# CntrlBoard.net
KiCad netlist of a schematic drawn in EAGLE
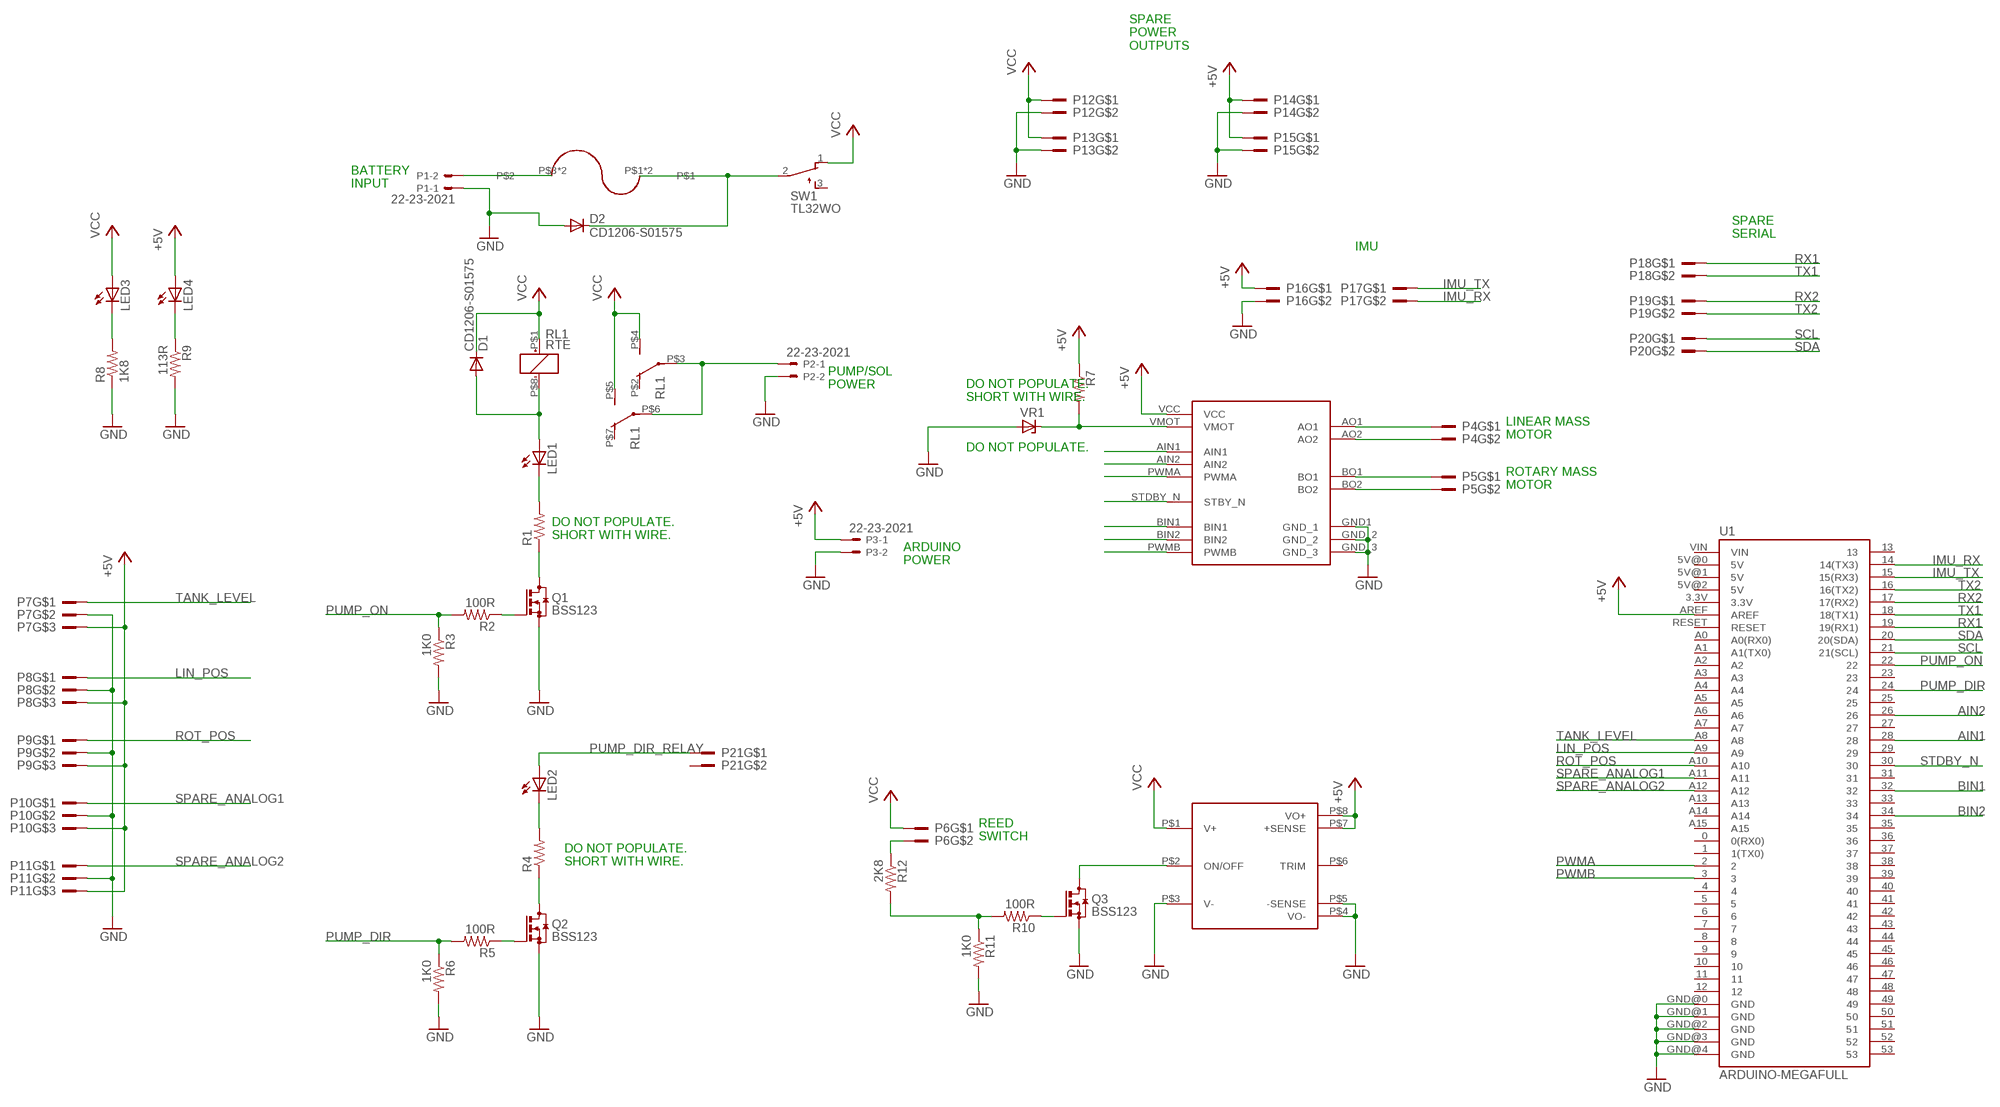
[diagram p0: schematic, sheet 1]

(export (version "E")
  (design (tool "Eeschema 10.0.6"))
  (components
    (comp (ref "D1")
      (value "CD1206-S01575")
      (footprint "eagle-import:CD1206")
      (libsource (lib "eagle-import") (part "CD1206-S01575"))
    )
    (comp (ref "D2")
      (value "CD1206-S01575")
      (footprint "eagle-import:CD1206")
      (libsource (lib "eagle-import") (part "CD1206-S01575"))
    )
    (comp (ref "LED1")
      (value "LEDCHIPLED_1206")
      (footprint "eagle-import:CHIPLED_1206")
      (libsource (lib "eagle-import") (part "LEDCHIPLED_1206"))
    )
    (comp (ref "LED2")
      (value "LEDCHIPLED_1206")
      (footprint "eagle-import:CHIPLED_1206")
      (libsource (lib "eagle-import") (part "LEDCHIPLED_1206"))
    )
    (comp (ref "LED3")
      (value "LEDCHIPLED_1206")
      (footprint "eagle-import:CHIPLED_1206")
      (libsource (lib "eagle-import") (part "LEDCHIPLED_1206"))
    )
    (comp (ref "LED4")
      (value "LEDCHIPLED_1206")
      (footprint "eagle-import:CHIPLED_1206")
      (libsource (lib "eagle-import") (part "LEDCHIPLED_1206"))
    )
    (comp (ref "P1")
      (value "22-23-2021")
      (footprint "eagle-import:22-23-2021")
      (fields (field (name "MF") "MOLEX"))
      (libsource (lib "eagle-import") (part "22-23-2021"))
    )
    (comp (ref "P2")
      (value "22-23-2021")
      (footprint "eagle-import:22-23-2021")
      (fields (field (name "MF") "MOLEX"))
      (libsource (lib "eagle-import") (part "22-23-2021"))
    )
    (comp (ref "P3")
      (value "22-23-2021")
      (footprint "eagle-import:22-23-2021")
      (fields (field (name "MF") "MOLEX"))
      (libsource (lib "eagle-import") (part "22-23-2021"))
    )
    (comp (ref "P4")
      (value "DF3A-2P-2DSA")
      (footprint "eagle-import:DF3A-2P-2DSA")
      (libsource (lib "eagle-import") (part "DF3A-2P-2DSA"))
    )
    (comp (ref "P5")
      (value "DF3A-2P-2DSA")
      (footprint "eagle-import:DF3A-2P-2DSA")
      (libsource (lib "eagle-import") (part "DF3A-2P-2DSA"))
    )
    (comp (ref "P6")
      (value "DF3A-2P-2DSA")
      (footprint "eagle-import:DF3A-2P-2DSA")
      (libsource (lib "eagle-import") (part "DF3A-2P-2DSA"))
    )
    (comp (ref "P7")
      (value "3PIN2MMPITCH")
      (footprint "eagle-import:3PIN_2MMPITCH")
      (libsource (lib "eagle-import") (part "3PIN2MMPITCH"))
    )
    (comp (ref "P8")
      (value "3PIN2MMPITCH")
      (footprint "eagle-import:3PIN_2MMPITCH")
      (libsource (lib "eagle-import") (part "3PIN2MMPITCH"))
    )
    (comp (ref "P9")
      (value "3PIN2MMPITCH")
      (footprint "eagle-import:3PIN_2MMPITCH")
      (libsource (lib "eagle-import") (part "3PIN2MMPITCH"))
    )
    (comp (ref "P10")
      (value "3PIN2MMPITCH")
      (footprint "eagle-import:3PIN_2MMPITCH")
      (libsource (lib "eagle-import") (part "3PIN2MMPITCH"))
    )
    (comp (ref "P11")
      (value "3PIN2MMPITCH")
      (footprint "eagle-import:3PIN_2MMPITCH")
      (libsource (lib "eagle-import") (part "3PIN2MMPITCH"))
    )
    (comp (ref "P12")
      (value "DF3A-2P-2DSA")
      (footprint "eagle-import:DF3A-2P-2DSA")
      (libsource (lib "eagle-import") (part "DF3A-2P-2DSA"))
    )
    (comp (ref "P13")
      (value "DF3A-2P-2DSA")
      (footprint "eagle-import:DF3A-2P-2DSA")
      (libsource (lib "eagle-import") (part "DF3A-2P-2DSA"))
    )
    (comp (ref "P14")
      (value "DF3A-2P-2DSA")
      (footprint "eagle-import:DF3A-2P-2DSA")
      (libsource (lib "eagle-import") (part "DF3A-2P-2DSA"))
    )
    (comp (ref "P15")
      (value "DF3A-2P-2DSA")
      (footprint "eagle-import:DF3A-2P-2DSA")
      (libsource (lib "eagle-import") (part "DF3A-2P-2DSA"))
    )
    (comp (ref "P16")
      (value "DF3A-2P-2DSA")
      (footprint "eagle-import:DF3A-2P-2DSA")
      (libsource (lib "eagle-import") (part "DF3A-2P-2DSA"))
    )
    (comp (ref "P17")
      (value "DF3A-2P-2DSA")
      (footprint "eagle-import:DF3A-2P-2DSA")
      (libsource (lib "eagle-import") (part "DF3A-2P-2DSA"))
    )
    (comp (ref "P18")
      (value "DF3A-2P-2DSA")
      (footprint "eagle-import:DF3A-2P-2DSA")
      (libsource (lib "eagle-import") (part "DF3A-2P-2DSA"))
    )
    (comp (ref "P19")
      (value "DF3A-2P-2DSA")
      (footprint "eagle-import:DF3A-2P-2DSA")
      (libsource (lib "eagle-import") (part "DF3A-2P-2DSA"))
    )
    (comp (ref "P20")
      (value "DF3A-2P-2DSA")
      (footprint "eagle-import:DF3A-2P-2DSA")
      (libsource (lib "eagle-import") (part "DF3A-2P-2DSA"))
    )
    (comp (ref "P21")
      (value "DF3A-2P-2DSA")
      (footprint "eagle-import:DF3A-2P-2DSA")
      (libsource (lib "eagle-import") (part "DF3A-2P-2DSA"))
    )
    (comp (ref "PS1")
      (value "KHHD006A0A41Z")
      (footprint "eagle-import:KHHD006A0A41Z")
      (libsource (lib "eagle-import") (part "KHHD006A0A41Z"))
    )
    (comp (ref "Q1")
      (value "BSS123")
      (footprint "eagle-import:SOT23")
      (libsource (lib "eagle-import") (part "BSS123"))
    )
    (comp (ref "Q2")
      (value "BSS123")
      (footprint "eagle-import:SOT23")
      (libsource (lib "eagle-import") (part "BSS123"))
    )
    (comp (ref "Q3")
      (value "BSS123")
      (footprint "eagle-import:SOT23")
      (libsource (lib "eagle-import") (part "BSS123"))
    )
    (comp (ref "R1")
      (value "R-US_R1206")
      (footprint "eagle-import:R1206")
      (libsource (lib "eagle-import") (part "R-US_R1206"))
    )
    (comp (ref "R2")
      (value "100R")
      (footprint "eagle-import:R1206")
      (libsource (lib "eagle-import") (part "R-US_R1206"))
    )
    (comp (ref "R3")
      (value "1K0")
      (footprint "eagle-import:R1206")
      (libsource (lib "eagle-import") (part "R-US_R1206"))
    )
    (comp (ref "R4")
      (value "R-US_R1206")
      (footprint "eagle-import:R1206")
      (libsource (lib "eagle-import") (part "R-US_R1206"))
    )
    (comp (ref "R5")
      (value "100R")
      (footprint "eagle-import:R1206")
      (libsource (lib "eagle-import") (part "R-US_R1206"))
    )
    (comp (ref "R6")
      (value "1K0")
      (footprint "eagle-import:R1206")
      (libsource (lib "eagle-import") (part "R-US_R1206"))
    )
    (comp (ref "R7")
      (value "R-US_R1206")
      (footprint "eagle-import:R1206")
      (libsource (lib "eagle-import") (part "R-US_R1206"))
    )
    (comp (ref "R8")
      (value "1K8")
      (footprint "eagle-import:R1210")
      (libsource (lib "eagle-import") (part "R-US_R1210"))
    )
    (comp (ref "R9")
      (value "113R")
      (footprint "eagle-import:R1206")
      (libsource (lib "eagle-import") (part "R-US_R1206"))
    )
    (comp (ref "R10")
      (value "100R")
      (footprint "eagle-import:R1206")
      (libsource (lib "eagle-import") (part "R-US_R1206"))
    )
    (comp (ref "R11")
      (value "1K0")
      (footprint "eagle-import:R1206")
      (libsource (lib "eagle-import") (part "R-US_R1206"))
    )
    (comp (ref "R12")
      (value "2K8")
      (footprint "eagle-import:R1206")
      (libsource (lib "eagle-import") (part "R-US_R1206"))
    )
    (comp (ref "RL1")
      (value "RTE")
      (footprint "eagle-import:RTE")
      (libsource (lib "eagle-import") (part "RTE"))
    )
    (comp (ref "SW1")
      (value "TL32WO")
      (footprint "eagle-import:TL3XWO")
      (libsource (lib "eagle-import") (part "TL32WO"))
    )
    (comp (ref "U$1")
      (value "ATC_FUSE_HOLDER")
      (footprint "eagle-import:FUSE_HOLDER_ATC")
      (libsource (lib "eagle-import") (part "ATC_FUSE_HOLDER"))
    )
    (comp (ref "U$2")
      (value "POLOLU713")
      (footprint "eagle-import:POLOLU713")
      (libsource (lib "eagle-import") (part "POLOLU713"))
    )
    (comp (ref "U1")
      (value "ARDUINO-MEGAFULL")
      (footprint "eagle-import:ARDUINO_MEGA")
      (libsource (lib "eagle-import") (part "ARDUINO-MEGAFULL"))
    )
    (comp (ref "VR1")
      (value "ZENER-DIODESOT23")
      (footprint "eagle-import:SOT23")
      (libsource (lib "eagle-import") (part "ZENER-DIODESOT23"))
    )
  )
  (nets
    (net (code "1") (name "+5V") (class "Default")
      (node (ref "LED4") (pin "A") (pinfunction "A_A") (pintype "passive"))
      (node (ref "P10") (pin "P$3") (pinfunction "KL_P$3") (pintype "passive"))
      (node (ref "P11") (pin "P$3") (pinfunction "KL_P$3") (pintype "passive"))
      (node (ref "P14") (pin "P$1") (pinfunction "KL_P$1") (pintype "passive"))
      (node (ref "P15") (pin "P$1") (pinfunction "KL_P$1") (pintype "passive"))
      (node (ref "P16") (pin "P$1") (pinfunction "KL_P$1") (pintype "passive"))
      (node (ref "P3") (pin "1") (pinfunction "S_1") (pintype "passive"))
      (node (ref "P7") (pin "P$3") (pinfunction "KL_P$3") (pintype "passive"))
      (node (ref "P8") (pin "P$3") (pinfunction "KL_P$3") (pintype "passive"))
      (node (ref "P9") (pin "P$3") (pinfunction "KL_P$3") (pintype "passive"))
      (node (ref "PS1") (pin "P$7") (pinfunction "+SENSE_P$7") (pintype "bidirectional"))
      (node (ref "PS1") (pin "P$8") (pinfunction "VO+_P$8") (pintype "bidirectional"))
      (node (ref "R7") (pin "1") (pinfunction "1_1") (pintype "passive"))
      (node (ref "U$2") (pin "VCC") (pinfunction "VCC_VCC") (pintype "bidirectional"))
      (node (ref "U1") (pin "AREF") (pinfunction "AREF_AREF") (pintype "bidirectional"))
    )
    (net (code "2") (name "/AIN1") (class "Default")
      (node (ref "U$2") (pin "AIN1") (pinfunction "AIN1_AIN1") (pintype "bidirectional"))
      (node (ref "U1") (pin "28") (pinfunction "28_28") (pintype "bidirectional"))
    )
    (net (code "3") (name "/AIN2") (class "Default")
      (node (ref "U$2") (pin "AIN2") (pinfunction "AIN2_AIN2") (pintype "bidirectional"))
      (node (ref "U1") (pin "26") (pinfunction "26_26") (pintype "bidirectional"))
    )
    (net (code "4") (name "/BIN1") (class "Default")
      (node (ref "U$2") (pin "BIN1") (pinfunction "BIN1_BIN1") (pintype "bidirectional"))
      (node (ref "U1") (pin "32") (pinfunction "32_32") (pintype "bidirectional"))
    )
    (net (code "5") (name "/BIN2") (class "Default")
      (node (ref "U$2") (pin "BIN2") (pinfunction "BIN2_BIN2") (pintype "bidirectional"))
      (node (ref "U1") (pin "34") (pinfunction "34_34") (pintype "bidirectional"))
    )
    (net (code "6") (name "/IMU_RX") (class "Default")
      (node (ref "P17") (pin "P$2") (pinfunction "KL_P$2") (pintype "passive"))
      (node (ref "U1") (pin "14") (pinfunction "14(TX3)_14") (pintype "bidirectional"))
    )
    (net (code "7") (name "/IMU_TX") (class "Default")
      (node (ref "P17") (pin "P$1") (pinfunction "KL_P$1") (pintype "passive"))
      (node (ref "U1") (pin "15") (pinfunction "15(RX3)_15") (pintype "bidirectional"))
    )
    (net (code "8") (name "/LIN_POS") (class "Default")
      (node (ref "P8") (pin "P$1") (pinfunction "KL_P$1") (pintype "passive"))
      (node (ref "U1") (pin "A9") (pinfunction "A9_A9") (pintype "bidirectional"))
    )
    (net (code "9") (name "/PUMP_DIR") (class "Default")
      (node (ref "R5") (pin "2") (pinfunction "2_2") (pintype "passive"))
      (node (ref "R6") (pin "1") (pinfunction "1_1") (pintype "passive"))
      (node (ref "U1") (pin "24") (pinfunction "24_24") (pintype "bidirectional"))
    )
    (net (code "10") (name "/PUMP_DIR_RELAY") (class "Default")
      (node (ref "LED2") (pin "A") (pinfunction "A_A") (pintype "passive"))
      (node (ref "P21") (pin "P$1") (pinfunction "KL_P$1") (pintype "passive"))
    )
    (net (code "11") (name "/PUMP_ON") (class "Default")
      (node (ref "R2") (pin "2") (pinfunction "2_2") (pintype "passive"))
      (node (ref "R3") (pin "1") (pinfunction "1_1") (pintype "passive"))
      (node (ref "U1") (pin "22") (pinfunction "22_22") (pintype "bidirectional"))
    )
    (net (code "12") (name "/PWMA") (class "Default")
      (node (ref "U$2") (pin "PWMA") (pinfunction "PWMA_PWMA") (pintype "bidirectional"))
      (node (ref "U1") (pin "2") (pinfunction "2_2") (pintype "bidirectional"))
    )
    (net (code "13") (name "/PWMB") (class "Default")
      (node (ref "U$2") (pin "PWMB") (pinfunction "PWMB_PWMB") (pintype "bidirectional"))
      (node (ref "U1") (pin "3") (pinfunction "3_3") (pintype "bidirectional"))
    )
    (net (code "14") (name "/ROT_POS") (class "Default")
      (node (ref "P9") (pin "P$1") (pinfunction "KL_P$1") (pintype "passive"))
      (node (ref "U1") (pin "A10") (pinfunction "A10_A10") (pintype "bidirectional"))
    )
    (net (code "15") (name "/RX1") (class "Default")
      (node (ref "P18") (pin "P$1") (pinfunction "KL_P$1") (pintype "passive"))
      (node (ref "U1") (pin "19") (pinfunction "19(RX1)_19") (pintype "bidirectional"))
    )
    (net (code "16") (name "/RX2") (class "Default")
      (node (ref "P19") (pin "P$1") (pinfunction "KL_P$1") (pintype "passive"))
      (node (ref "U1") (pin "17") (pinfunction "17(RX2)_17") (pintype "bidirectional"))
    )
    (net (code "17") (name "/SCL") (class "Default")
      (node (ref "P20") (pin "P$1") (pinfunction "KL_P$1") (pintype "passive"))
      (node (ref "U1") (pin "21") (pinfunction "21(SCL)_21") (pintype "bidirectional"))
    )
    (net (code "18") (name "/SDA") (class "Default")
      (node (ref "P20") (pin "P$2") (pinfunction "KL_P$2") (pintype "passive"))
      (node (ref "U1") (pin "20") (pinfunction "20(SDA)_20") (pintype "bidirectional"))
    )
    (net (code "19") (name "/SPARE_ANALOG1") (class "Default")
      (node (ref "P10") (pin "P$1") (pinfunction "KL_P$1") (pintype "passive"))
      (node (ref "U1") (pin "A11") (pinfunction "A11_A11") (pintype "bidirectional"))
    )
    (net (code "20") (name "/SPARE_ANALOG2") (class "Default")
      (node (ref "P11") (pin "P$1") (pinfunction "KL_P$1") (pintype "passive"))
      (node (ref "U1") (pin "A12") (pinfunction "A12_A12") (pintype "bidirectional"))
    )
    (net (code "21") (name "/STDBY_N") (class "Default")
      (node (ref "U$2") (pin "STDBY_N") (pinfunction "STBY_N_STDBY_N") (pintype "bidirectional"))
      (node (ref "U1") (pin "30") (pinfunction "30_30") (pintype "bidirectional"))
    )
    (net (code "22") (name "/TANK_LEVEL") (class "Default")
      (node (ref "P7") (pin "P$1") (pinfunction "KL_P$1") (pintype "passive"))
      (node (ref "U1") (pin "A8") (pinfunction "A8_A8") (pintype "bidirectional"))
    )
    (net (code "23") (name "/TX1") (class "Default")
      (node (ref "P18") (pin "P$2") (pinfunction "KL_P$2") (pintype "passive"))
      (node (ref "U1") (pin "18") (pinfunction "18(TX1)_18") (pintype "bidirectional"))
    )
    (net (code "24") (name "/TX2") (class "Default")
      (node (ref "P19") (pin "P$2") (pinfunction "KL_P$2") (pintype "passive"))
      (node (ref "U1") (pin "16") (pinfunction "16(TX2)_16") (pintype "bidirectional"))
    )
    (net (code "25") (name "GND") (class "Default")
      (node (ref "D2") (pin "A") (pinfunction "A_A") (pintype "passive"))
      (node (ref "P1") (pin "1") (pinfunction "S_1") (pintype "passive"))
      (node (ref "P10") (pin "P$2") (pinfunction "KL_P$2") (pintype "passive"))
      (node (ref "P11") (pin "P$2") (pinfunction "KL_P$2") (pintype "passive"))
      (node (ref "P12") (pin "P$2") (pinfunction "KL_P$2") (pintype "passive"))
      (node (ref "P13") (pin "P$2") (pinfunction "KL_P$2") (pintype "passive"))
      (node (ref "P14") (pin "P$2") (pinfunction "KL_P$2") (pintype "passive"))
      (node (ref "P15") (pin "P$2") (pinfunction "KL_P$2") (pintype "passive"))
      (node (ref "P16") (pin "P$2") (pinfunction "KL_P$2") (pintype "passive"))
      (node (ref "P2") (pin "2") (pinfunction "S_2") (pintype "passive"))
      (node (ref "P3") (pin "2") (pinfunction "S_2") (pintype "passive"))
      (node (ref "P7") (pin "P$2") (pinfunction "KL_P$2") (pintype "passive"))
      (node (ref "P8") (pin "P$2") (pinfunction "KL_P$2") (pintype "passive"))
      (node (ref "P9") (pin "P$2") (pinfunction "KL_P$2") (pintype "passive"))
      (node (ref "PS1") (pin "P$3") (pinfunction "V-_P$3") (pintype "bidirectional"))
      (node (ref "PS1") (pin "P$4") (pinfunction "VO-_P$4") (pintype "bidirectional"))
      (node (ref "PS1") (pin "P$5") (pinfunction "-SENSE_P$5") (pintype "bidirectional"))
      (node (ref "Q1") (pin "2") (pinfunction "S_2") (pintype "passive"))
      (node (ref "Q2") (pin "2") (pinfunction "S_2") (pintype "passive"))
      (node (ref "Q3") (pin "2") (pinfunction "S_2") (pintype "passive"))
      (node (ref "R11") (pin "2") (pinfunction "2_2") (pintype "passive"))
      (node (ref "R3") (pin "2") (pinfunction "2_2") (pintype "passive"))
      (node (ref "R6") (pin "2") (pinfunction "2_2") (pintype "passive"))
      (node (ref "R8") (pin "1") (pinfunction "1_1") (pintype "passive"))
      (node (ref "R9") (pin "2") (pinfunction "2_2") (pintype "passive"))
      (node (ref "U$2") (pin "GND1") (pinfunction "GND_1_GND1") (pintype "bidirectional"))
      (node (ref "U$2") (pin "GND_2") (pinfunction "GND_2_GND_2") (pintype "bidirectional"))
      (node (ref "U$2") (pin "GND_3") (pinfunction "GND_3_GND_3") (pintype "bidirectional"))
      (node (ref "U1") (pin "GND@0") (pinfunction "GND_GND@0") (pintype "bidirectional"))
      (node (ref "U1") (pin "GND@1") (pinfunction "GND_GND@1") (pintype "bidirectional"))
      (node (ref "U1") (pin "GND@2") (pinfunction "GND_GND@2") (pintype "bidirectional"))
      (node (ref "U1") (pin "GND@3") (pinfunction "GND_GND@3") (pintype "bidirectional"))
      (node (ref "U1") (pin "GND@4") (pinfunction "GND_GND@4") (pintype "bidirectional"))
      (node (ref "VR1") (pin "1") (pinfunction "A_1") (pintype "passive"))
    )
    (net (code "26") (name "Net-(D2-C)") (class "Default")
      (node (ref "D2") (pin "K") (pinfunction "C_K") (pintype "passive"))
      (node (ref "SW1") (pin "2") (pinfunction "P_2") (pintype "passive"))
      (node (ref "U$1") (pin "P$1") (pinfunction "P$1_P$1") (pintype "bidirectional"))
      (node (ref "U$1") (pin "P$2") (pinfunction "P$1_P$2") (pintype "bidirectional"))
    )
    (net (code "27") (name "Net-(LED1-PadC)") (class "Default")
      (node (ref "LED1") (pin "C") (pinfunction "C_C") (pintype "passive"))
      (node (ref "R1") (pin "2") (pinfunction "2_2") (pintype "passive"))
    )
    (net (code "28") (name "Net-(LED2-PadC)") (class "Default")
      (node (ref "LED2") (pin "C") (pinfunction "C_C") (pintype "passive"))
      (node (ref "R4") (pin "2") (pinfunction "2_2") (pintype "passive"))
    )
    (net (code "29") (name "Net-(LED3-PadC)") (class "Default")
      (node (ref "LED3") (pin "C") (pinfunction "C_C") (pintype "passive"))
      (node (ref "R8") (pin "2") (pinfunction "2_2") (pintype "passive"))
    )
    (net (code "30") (name "Net-(LED4-PadC)") (class "Default")
      (node (ref "LED4") (pin "C") (pinfunction "C_C") (pintype "passive"))
      (node (ref "R9") (pin "1") (pinfunction "1_1") (pintype "passive"))
    )
    (net (code "31") (name "Net-(P1B-S)") (class "Default")
      (node (ref "P1") (pin "2") (pinfunction "S_2") (pintype "passive"))
      (node (ref "U$1") (pin "P$3") (pinfunction "P$2_P$3") (pintype "bidirectional"))
      (node (ref "U$1") (pin "P$4") (pinfunction "P$2_P$4") (pintype "bidirectional"))
    )
    (net (code "32") (name "Net-(P2A-S)") (class "Default")
      (node (ref "P2") (pin "1") (pinfunction "S_1") (pintype "passive"))
      (node (ref "RL1") (pin "P$3") (pinfunction "P_P$3") (pintype "passive"))
      (node (ref "RL1") (pin "P$6") (pinfunction "P_P$6") (pintype "passive"))
    )
    (net (code "33") (name "Net-(P4A-KL)") (class "Default")
      (node (ref "P4") (pin "P$1") (pinfunction "KL_P$1") (pintype "passive"))
      (node (ref "U$2") (pin "AO1") (pinfunction "AO1_AO1") (pintype "bidirectional"))
    )
    (net (code "34") (name "Net-(P4B-KL)") (class "Default")
      (node (ref "P4") (pin "P$2") (pinfunction "KL_P$2") (pintype "passive"))
      (node (ref "U$2") (pin "AO2") (pinfunction "AO2_AO2") (pintype "bidirectional"))
    )
    (net (code "35") (name "Net-(P5A-KL)") (class "Default")
      (node (ref "P5") (pin "P$1") (pinfunction "KL_P$1") (pintype "passive"))
      (node (ref "U$2") (pin "BO1") (pinfunction "BO1_BO1") (pintype "bidirectional"))
    )
    (net (code "36") (name "Net-(P5B-KL)") (class "Default")
      (node (ref "P5") (pin "P$2") (pinfunction "KL_P$2") (pintype "passive"))
      (node (ref "U$2") (pin "BO2") (pinfunction "BO2_BO2") (pintype "bidirectional"))
    )
    (net (code "37") (name "Net-(P6B-KL)") (class "Default")
      (node (ref "P6") (pin "P$2") (pinfunction "KL_P$2") (pintype "passive"))
      (node (ref "R12") (pin "1") (pinfunction "1_1") (pintype "passive"))
    )
    (net (code "38") (name "Net-(PS1-ON{slash}OFF)") (class "Default")
      (node (ref "PS1") (pin "P$2") (pinfunction "ON/OFF_P$2") (pintype "bidirectional"))
      (node (ref "Q3") (pin "3") (pinfunction "D_3") (pintype "passive"))
    )
    (net (code "39") (name "Net-(Q1-D)") (class "Default")
      (node (ref "Q1") (pin "3") (pinfunction "D_3") (pintype "passive"))
      (node (ref "R1") (pin "1") (pinfunction "1_1") (pintype "passive"))
    )
    (net (code "40") (name "Net-(Q1-G)") (class "Default")
      (node (ref "Q1") (pin "1") (pinfunction "G_1") (pintype "passive"))
      (node (ref "R2") (pin "1") (pinfunction "1_1") (pintype "passive"))
    )
    (net (code "41") (name "Net-(Q2-D)") (class "Default")
      (node (ref "Q2") (pin "3") (pinfunction "D_3") (pintype "passive"))
      (node (ref "R4") (pin "1") (pinfunction "1_1") (pintype "passive"))
    )
    (net (code "42") (name "Net-(Q2-G)") (class "Default")
      (node (ref "Q2") (pin "1") (pinfunction "G_1") (pintype "passive"))
      (node (ref "R5") (pin "1") (pinfunction "1_1") (pintype "passive"))
    )
    (net (code "43") (name "Net-(Q3-G)") (class "Default")
      (node (ref "Q3") (pin "1") (pinfunction "G_1") (pintype "passive"))
      (node (ref "R10") (pin "1") (pinfunction "1_1") (pintype "passive"))
    )
    (net (code "44") (name "Net-(R10-Pad2)") (class "Default")
      (node (ref "R10") (pin "2") (pinfunction "2_2") (pintype "passive"))
      (node (ref "R11") (pin "1") (pinfunction "1_1") (pintype "passive"))
      (node (ref "R12") (pin "2") (pinfunction "2_2") (pintype "passive"))
    )
    (net (code "45") (name "Net-(RL1A--)") (class "Default")
      (node (ref "D1") (pin "A") (pinfunction "A_A") (pintype "passive"))
      (node (ref "LED1") (pin "A") (pinfunction "A_A") (pintype "passive"))
      (node (ref "RL1") (pin "P$8") (pinfunction "-_P$8") (pintype "passive"))
    )
    (net (code "46") (name "Net-(VR1-C)") (class "Default")
      (node (ref "R7") (pin "2") (pinfunction "2_2") (pintype "passive"))
      (node (ref "U$2") (pin "VMOT") (pinfunction "VMOT_VMOT") (pintype "bidirectional"))
      (node (ref "VR1") (pin "3") (pinfunction "C_3") (pintype "passive"))
    )
    (net (code "47") (name "VCC") (class "Default")
      (node (ref "D1") (pin "K") (pinfunction "C_K") (pintype "passive"))
      (node (ref "LED3") (pin "A") (pinfunction "A_A") (pintype "passive"))
      (node (ref "P12") (pin "P$1") (pinfunction "KL_P$1") (pintype "passive"))
      (node (ref "P13") (pin "P$1") (pinfunction "KL_P$1") (pintype "passive"))
      (node (ref "P6") (pin "P$1") (pinfunction "KL_P$1") (pintype "passive"))
      (node (ref "PS1") (pin "P$1") (pinfunction "V+_P$1") (pintype "bidirectional"))
      (node (ref "RL1") (pin "P$1") (pinfunction "+_P$1") (pintype "passive"))
      (node (ref "RL1") (pin "P$4") (pinfunction "S_P$4") (pintype "passive"))
      (node (ref "RL1") (pin "P$5") (pinfunction "S_P$5") (pintype "passive"))
      (node (ref "SW1") (pin "1") (pinfunction "O_1") (pintype "passive"))
    )
    (net (code "48") (name "unconnected-(P21B-KL-PadP$2)") (class "Default")
      (node (ref "P21") (pin "P$2") (pinfunction "KL_P$2") (pintype "passive"))
    )
    (net (code "49") (name "unconnected-(PS1-TRIM-PadP$6)") (class "Default")
      (node (ref "PS1") (pin "P$6") (pinfunction "TRIM_P$6") (pintype "bidirectional"))
    )
    (net (code "50") (name "unconnected-(RL1B-O-PadP$2)") (class "Default")
      (node (ref "RL1") (pin "P$2") (pinfunction "O_P$2") (pintype "passive"))
    )
    (net (code "51") (name "unconnected-(RL1C-O-PadP$7)") (class "Default")
      (node (ref "RL1") (pin "P$7") (pinfunction "O_P$7") (pintype "passive"))
    )
    (net (code "52") (name "unconnected-(SW1-S-Pad3)") (class "Default")
      (node (ref "SW1") (pin "3") (pinfunction "S_3") (pintype "passive"))
    )
    (net (code "53") (name "unconnected-(U1-0(RX0)-Pad0)") (class "Default")
      (node (ref "U1") (pin "0") (pinfunction "0(RX0)_0") (pintype "bidirectional"))
    )
    (net (code "54") (name "unconnected-(U1-1(TX0)-Pad1)") (class "Default")
      (node (ref "U1") (pin "1") (pinfunction "1(TX0)_1") (pintype "bidirectional"))
    )
    (net (code "55") (name "unconnected-(U1-5V-Pad5V@0)") (class "Default")
      (node (ref "U1") (pin "5V@0") (pinfunction "5V_5V@0") (pintype "bidirectional"))
    )
    (net (code "56") (name "unconnected-(U1-5V-Pad5V@1)") (class "Default")
      (node (ref "U1") (pin "5V@1") (pinfunction "5V_5V@1") (pintype "bidirectional"))
    )
    (net (code "57") (name "unconnected-(U1-5V-Pad5V@2)") (class "Default")
      (node (ref "U1") (pin "5V@2") (pinfunction "5V_5V@2") (pintype "bidirectional"))
    )
    (net (code "58") (name "unconnected-(U1-A0(RX0)-PadA0)") (class "Default")
      (node (ref "U1") (pin "A0") (pinfunction "A0(RX0)_A0") (pintype "bidirectional"))
    )
    (net (code "59") (name "unconnected-(U1-A1(TX0)-PadA1)") (class "Default")
      (node (ref "U1") (pin "A1") (pinfunction "A1(TX0)_A1") (pintype "bidirectional"))
    )
    (net (code "60") (name "unconnected-(U1-Pad3.3V)") (class "Default")
      (node (ref "U1") (pin "3.3V") (pinfunction "3.3V_3.3V") (pintype "bidirectional"))
    )
    (net (code "61") (name "unconnected-(U1-Pad4)") (class "Default")
      (node (ref "U1") (pin "4") (pinfunction "4_4") (pintype "bidirectional"))
    )
    (net (code "62") (name "unconnected-(U1-Pad5)") (class "Default")
      (node (ref "U1") (pin "5") (pinfunction "5_5") (pintype "bidirectional"))
    )
    (net (code "63") (name "unconnected-(U1-Pad6)") (class "Default")
      (node (ref "U1") (pin "6") (pinfunction "6_6") (pintype "bidirectional"))
    )
    (net (code "64") (name "unconnected-(U1-Pad7)") (class "Default")
      (node (ref "U1") (pin "7") (pinfunction "7_7") (pintype "bidirectional"))
    )
    (net (code "65") (name "unconnected-(U1-Pad8)") (class "Default")
      (node (ref "U1") (pin "8") (pinfunction "8_8") (pintype "bidirectional"))
    )
    (net (code "66") (name "unconnected-(U1-Pad9)") (class "Default")
      (node (ref "U1") (pin "9") (pinfunction "9_9") (pintype "bidirectional"))
    )
    (net (code "67") (name "unconnected-(U1-Pad10)") (class "Default")
      (node (ref "U1") (pin "10") (pinfunction "10_10") (pintype "bidirectional"))
    )
    (net (code "68") (name "unconnected-(U1-Pad11)") (class "Default")
      (node (ref "U1") (pin "11") (pinfunction "11_11") (pintype "bidirectional"))
    )
    (net (code "69") (name "unconnected-(U1-Pad12)") (class "Default")
      (node (ref "U1") (pin "12") (pinfunction "12_12") (pintype "bidirectional"))
    )
    (net (code "70") (name "unconnected-(U1-Pad13)") (class "Default")
      (node (ref "U1") (pin "13") (pinfunction "13_13") (pintype "bidirectional"))
    )
    (net (code "71") (name "unconnected-(U1-Pad23)") (class "Default")
      (node (ref "U1") (pin "23") (pinfunction "23_23") (pintype "bidirectional"))
    )
    (net (code "72") (name "unconnected-(U1-Pad25)") (class "Default")
      (node (ref "U1") (pin "25") (pinfunction "25_25") (pintype "bidirectional"))
    )
    (net (code "73") (name "unconnected-(U1-Pad27)") (class "Default")
      (node (ref "U1") (pin "27") (pinfunction "27_27") (pintype "bidirectional"))
    )
    (net (code "74") (name "unconnected-(U1-Pad29)") (class "Default")
      (node (ref "U1") (pin "29") (pinfunction "29_29") (pintype "bidirectional"))
    )
    (net (code "75") (name "unconnected-(U1-Pad31)") (class "Default")
      (node (ref "U1") (pin "31") (pinfunction "31_31") (pintype "bidirectional"))
    )
    (net (code "76") (name "unconnected-(U1-Pad33)") (class "Default")
      (node (ref "U1") (pin "33") (pinfunction "33_33") (pintype "bidirectional"))
    )
    (net (code "77") (name "unconnected-(U1-Pad35)") (class "Default")
      (node (ref "U1") (pin "35") (pinfunction "35_35") (pintype "bidirectional"))
    )
    (net (code "78") (name "unconnected-(U1-Pad36)") (class "Default")
      (node (ref "U1") (pin "36") (pinfunction "36_36") (pintype "bidirectional"))
    )
    (net (code "79") (name "unconnected-(U1-Pad37)") (class "Default")
      (node (ref "U1") (pin "37") (pinfunction "37_37") (pintype "bidirectional"))
    )
    (net (code "80") (name "unconnected-(U1-Pad38)") (class "Default")
      (node (ref "U1") (pin "38") (pinfunction "38_38") (pintype "bidirectional"))
    )
    (net (code "81") (name "unconnected-(U1-Pad39)") (class "Default")
      (node (ref "U1") (pin "39") (pinfunction "39_39") (pintype "bidirectional"))
    )
    (net (code "82") (name "unconnected-(U1-Pad40)") (class "Default")
      (node (ref "U1") (pin "40") (pinfunction "40_40") (pintype "bidirectional"))
    )
    (net (code "83") (name "unconnected-(U1-Pad41)") (class "Default")
      (node (ref "U1") (pin "41") (pinfunction "41_41") (pintype "bidirectional"))
    )
    (net (code "84") (name "unconnected-(U1-Pad42)") (class "Default")
      (node (ref "U1") (pin "42") (pinfunction "42_42") (pintype "bidirectional"))
    )
    (net (code "85") (name "unconnected-(U1-Pad43)") (class "Default")
      (node (ref "U1") (pin "43") (pinfunction "43_43") (pintype "bidirectional"))
    )
    (net (code "86") (name "unconnected-(U1-Pad44)") (class "Default")
      (node (ref "U1") (pin "44") (pinfunction "44_44") (pintype "bidirectional"))
    )
    (net (code "87") (name "unconnected-(U1-Pad45)") (class "Default")
      (node (ref "U1") (pin "45") (pinfunction "45_45") (pintype "bidirectional"))
    )
    (net (code "88") (name "unconnected-(U1-Pad46)") (class "Default")
      (node (ref "U1") (pin "46") (pinfunction "46_46") (pintype "bidirectional"))
    )
    (net (code "89") (name "unconnected-(U1-Pad47)") (class "Default")
      (node (ref "U1") (pin "47") (pinfunction "47_47") (pintype "bidirectional"))
    )
    (net (code "90") (name "unconnected-(U1-Pad48)") (class "Default")
      (node (ref "U1") (pin "48") (pinfunction "48_48") (pintype "bidirectional"))
    )
    (net (code "91") (name "unconnected-(U1-Pad49)") (class "Default")
      (node (ref "U1") (pin "49") (pinfunction "49_49") (pintype "bidirectional"))
    )
    (net (code "92") (name "unconnected-(U1-Pad50)") (class "Default")
      (node (ref "U1") (pin "50") (pinfunction "50_50") (pintype "bidirectional"))
    )
    (net (code "93") (name "unconnected-(U1-Pad51)") (class "Default")
      (node (ref "U1") (pin "51") (pinfunction "51_51") (pintype "bidirectional"))
    )
    (net (code "94") (name "unconnected-(U1-Pad52)") (class "Default")
      (node (ref "U1") (pin "52") (pinfunction "52_52") (pintype "bidirectional"))
    )
    (net (code "95") (name "unconnected-(U1-Pad53)") (class "Default")
      (node (ref "U1") (pin "53") (pinfunction "53_53") (pintype "bidirectional"))
    )
    (net (code "96") (name "unconnected-(U1-PadA2)") (class "Default")
      (node (ref "U1") (pin "A2") (pinfunction "A2_A2") (pintype "bidirectional"))
    )
    (net (code "97") (name "unconnected-(U1-PadA3)") (class "Default")
      (node (ref "U1") (pin "A3") (pinfunction "A3_A3") (pintype "bidirectional"))
    )
    (net (code "98") (name "unconnected-(U1-PadA4)") (class "Default")
      (node (ref "U1") (pin "A4") (pinfunction "A4_A4") (pintype "bidirectional"))
    )
    (net (code "99") (name "unconnected-(U1-PadA5)") (class "Default")
      (node (ref "U1") (pin "A5") (pinfunction "A5_A5") (pintype "bidirectional"))
    )
    (net (code "100") (name "unconnected-(U1-PadA6)") (class "Default")
      (node (ref "U1") (pin "A6") (pinfunction "A6_A6") (pintype "bidirectional"))
    )
    (net (code "101") (name "unconnected-(U1-PadA7)") (class "Default")
      (node (ref "U1") (pin "A7") (pinfunction "A7_A7") (pintype "bidirectional"))
    )
    (net (code "102") (name "unconnected-(U1-PadA13)") (class "Default")
      (node (ref "U1") (pin "A13") (pinfunction "A13_A13") (pintype "bidirectional"))
    )
    (net (code "103") (name "unconnected-(U1-PadA14)") (class "Default")
      (node (ref "U1") (pin "A14") (pinfunction "A14_A14") (pintype "bidirectional"))
    )
    (net (code "104") (name "unconnected-(U1-PadA15)") (class "Default")
      (node (ref "U1") (pin "A15") (pinfunction "A15_A15") (pintype "bidirectional"))
    )
    (net (code "105") (name "unconnected-(U1-PadRESET)") (class "Default")
      (node (ref "U1") (pin "RESET") (pinfunction "RESET_RESET") (pintype "bidirectional"))
    )
    (net (code "106") (name "unconnected-(U1-PadVIN)") (class "Default")
      (node (ref "U1") (pin "VIN") (pinfunction "VIN_VIN") (pintype "bidirectional"))
    )
  )
)
